# RS485.net
KiCad netlist of a schematic drawn in Altium Designer
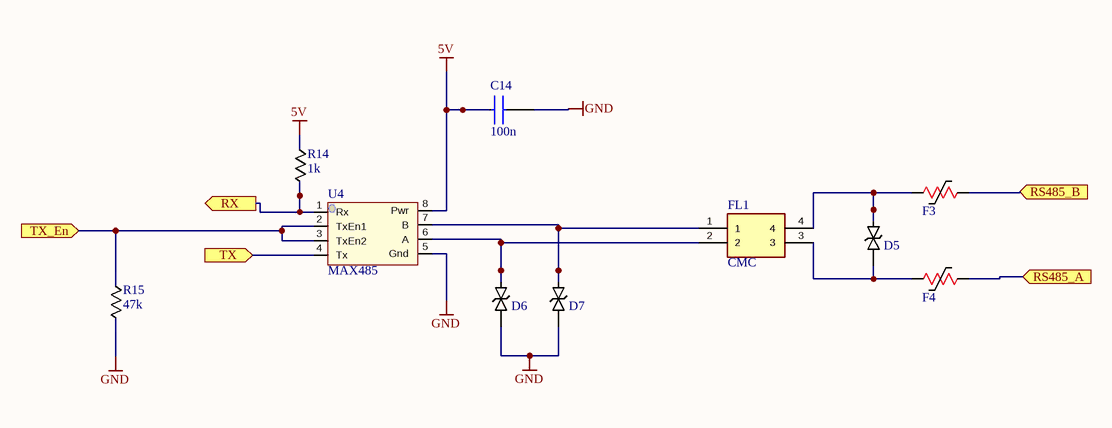
[diagram p0: RS485.SchDoc]

(export (version "E")
  (design (tool "Eeschema 10.0.6"))
  (components
    (comp (ref "C14")
      (value "100n")
      (footprint "0603 CAP")
      (description "CC0603KRX7R9BB104")
      (fields
        (field (name "MANUFACTURER_PART_NUMBER") "GRM188R72A103KA01D")
        (field (name "MOUSER PART NUMBER") "81-GRM188R72A103KA1D")
      )
      (libsource (lib "IGAS Elements") (part "0603 CAP"))
    )
    (comp (ref "D5")
      (value "TVS Diode")
      (footprint "DO-214AC / SMA")
      (description "TVS Protective Diode")
      (libsource (lib "IGAS Elements") (part "TVS"))
    )
    (comp (ref "D6")
      (value "TVS Diode")
      (footprint "DO-214AC / SMA")
      (description "TVS Protective Diode")
      (libsource (lib "IGAS Elements") (part "TVS"))
    )
    (comp (ref "D7")
      (value "TVS Diode")
      (footprint "DO-214AC / SMA")
      (description "TVS Protective Diode")
      (libsource (lib "IGAS Elements") (part "TVS"))
    )
    (comp (ref "F3")
      (value "MF-USMF005-2")
      (footprint "MF-MSMF030-2")
      (description "Resettable Fuse Polyswitch")
      (libsource (lib "IGAS Elements") (part "Fuse Resettable"))
    )
    (comp (ref "F4")
      (value "MF-USMF005-2")
      (footprint "MF-MSMF030-2")
      (description "Resettable Fuse Polyswitch")
      (libsource (lib "IGAS Elements") (part "Fuse Resettable"))
    )
    (comp (ref "FL1")
      (value "CMC")
      (footprint "IGAS Elements:ACM20129002PT002")
      (description "ACM2012-900-2P-T002")
      (fields (field (name "MOUSER PART NUMBER") "810-ACM20129002PT002"))
      (libsource (lib "IGAS Elements") (part "ACM2012-900-2P-T002"))
    )
    (comp (ref "R14") (value "1k") (footprint "0603 CAP") (libsource (lib "IGAS Elements") (part "0603 RES")))
    (comp (ref "R15")
      (value "47k")
      (footprint "0603 CAP")
      (description "RC0603FR-0747KL")
      (libsource (lib "IGAS Elements") (part "0603 RES"))
    )
    (comp (ref "U4") (value "MAX485") (footprint "SOIC-8") (libsource (lib "IGAS Elements") (part "MAX485")))
  )
  (nets
    (net (code "1") (name "/RS485_A") (class "Default")
      (node (ref "F4") (pin "1") (pinfunction "1_1") (pintype "passive"))
    )
    (net (code "2") (name "/RS485_B") (class "Default")
      (node (ref "F3") (pin "1") (pinfunction "1_1") (pintype "passive"))
    )
    (net (code "3") (name "/RX") (class "Default")
      (node (ref "R14") (pin "2") (pintype "passive"))
      (node (ref "U4") (pin "1") (pinfunction "Rx_1") (pintype "passive"))
    )
    (net (code "4") (name "/TX") (class "Default")
      (node (ref "U4") (pin "4") (pinfunction "Tx_4") (pintype "passive"))
    )
    (net (code "5") (name "/TX_En") (class "Default")
      (node (ref "R15") (pin "1") (pintype "passive"))
      (node (ref "U4") (pin "2") (pinfunction "TxEn1_2") (pintype "passive"))
      (node (ref "U4") (pin "3") (pinfunction "TxEn2_3") (pintype "passive"))
    )
    (net (code "6") (name "5V") (class "Default")
      (node (ref "C14") (pin "2") (pinfunction "2_2") (pintype "passive"))
      (node (ref "R14") (pin "1") (pintype "passive"))
      (node (ref "U4") (pin "8") (pinfunction "Pwr_8") (pintype "passive"))
    )
    (net (code "7") (name "GND") (class "Default")
      (node (ref "C14") (pin "1") (pinfunction "1_1") (pintype "passive"))
      (node (ref "D6") (pin "1") (pinfunction "1_1") (pintype "passive"))
      (node (ref "D7") (pin "1") (pinfunction "1_1") (pintype "passive"))
      (node (ref "R15") (pin "2") (pintype "passive"))
      (node (ref "U4") (pin "5") (pinfunction "Gnd_5") (pintype "passive"))
    )
    (net (code "8") (name "Net-(D5-Pad1)") (class "Default")
      (node (ref "D5") (pin "1") (pinfunction "1_1") (pintype "passive"))
      (node (ref "F4") (pin "2") (pinfunction "2_2") (pintype "passive"))
      (node (ref "FL1") (pin "3") (pinfunction "3_3") (pintype "passive"))
    )
    (net (code "9") (name "Net-(D5-Pad2)") (class "Default")
      (node (ref "D5") (pin "2") (pinfunction "2_2") (pintype "passive"))
      (node (ref "F3") (pin "2") (pinfunction "2_2") (pintype "passive"))
      (node (ref "FL1") (pin "4") (pinfunction "4_4") (pintype "passive"))
    )
    (net (code "10") (name "Net-(U4-A)") (class "Default")
      (node (ref "D6") (pin "2") (pinfunction "2_2") (pintype "passive"))
      (node (ref "FL1") (pin "2") (pinfunction "2_2") (pintype "passive"))
      (node (ref "U4") (pin "6") (pinfunction "A_6") (pintype "passive"))
    )
    (net (code "11") (name "Net-(U4-B)") (class "Default")
      (node (ref "D7") (pin "2") (pinfunction "2_2") (pintype "passive"))
      (node (ref "FL1") (pin "1") (pinfunction "1_1") (pintype "passive"))
      (node (ref "U4") (pin "7") (pinfunction "B_7") (pintype "passive"))
    )
  )
)
